# RFM69Pi_V3_1.net
KiCad netlist of a schematic drawn in EAGLE
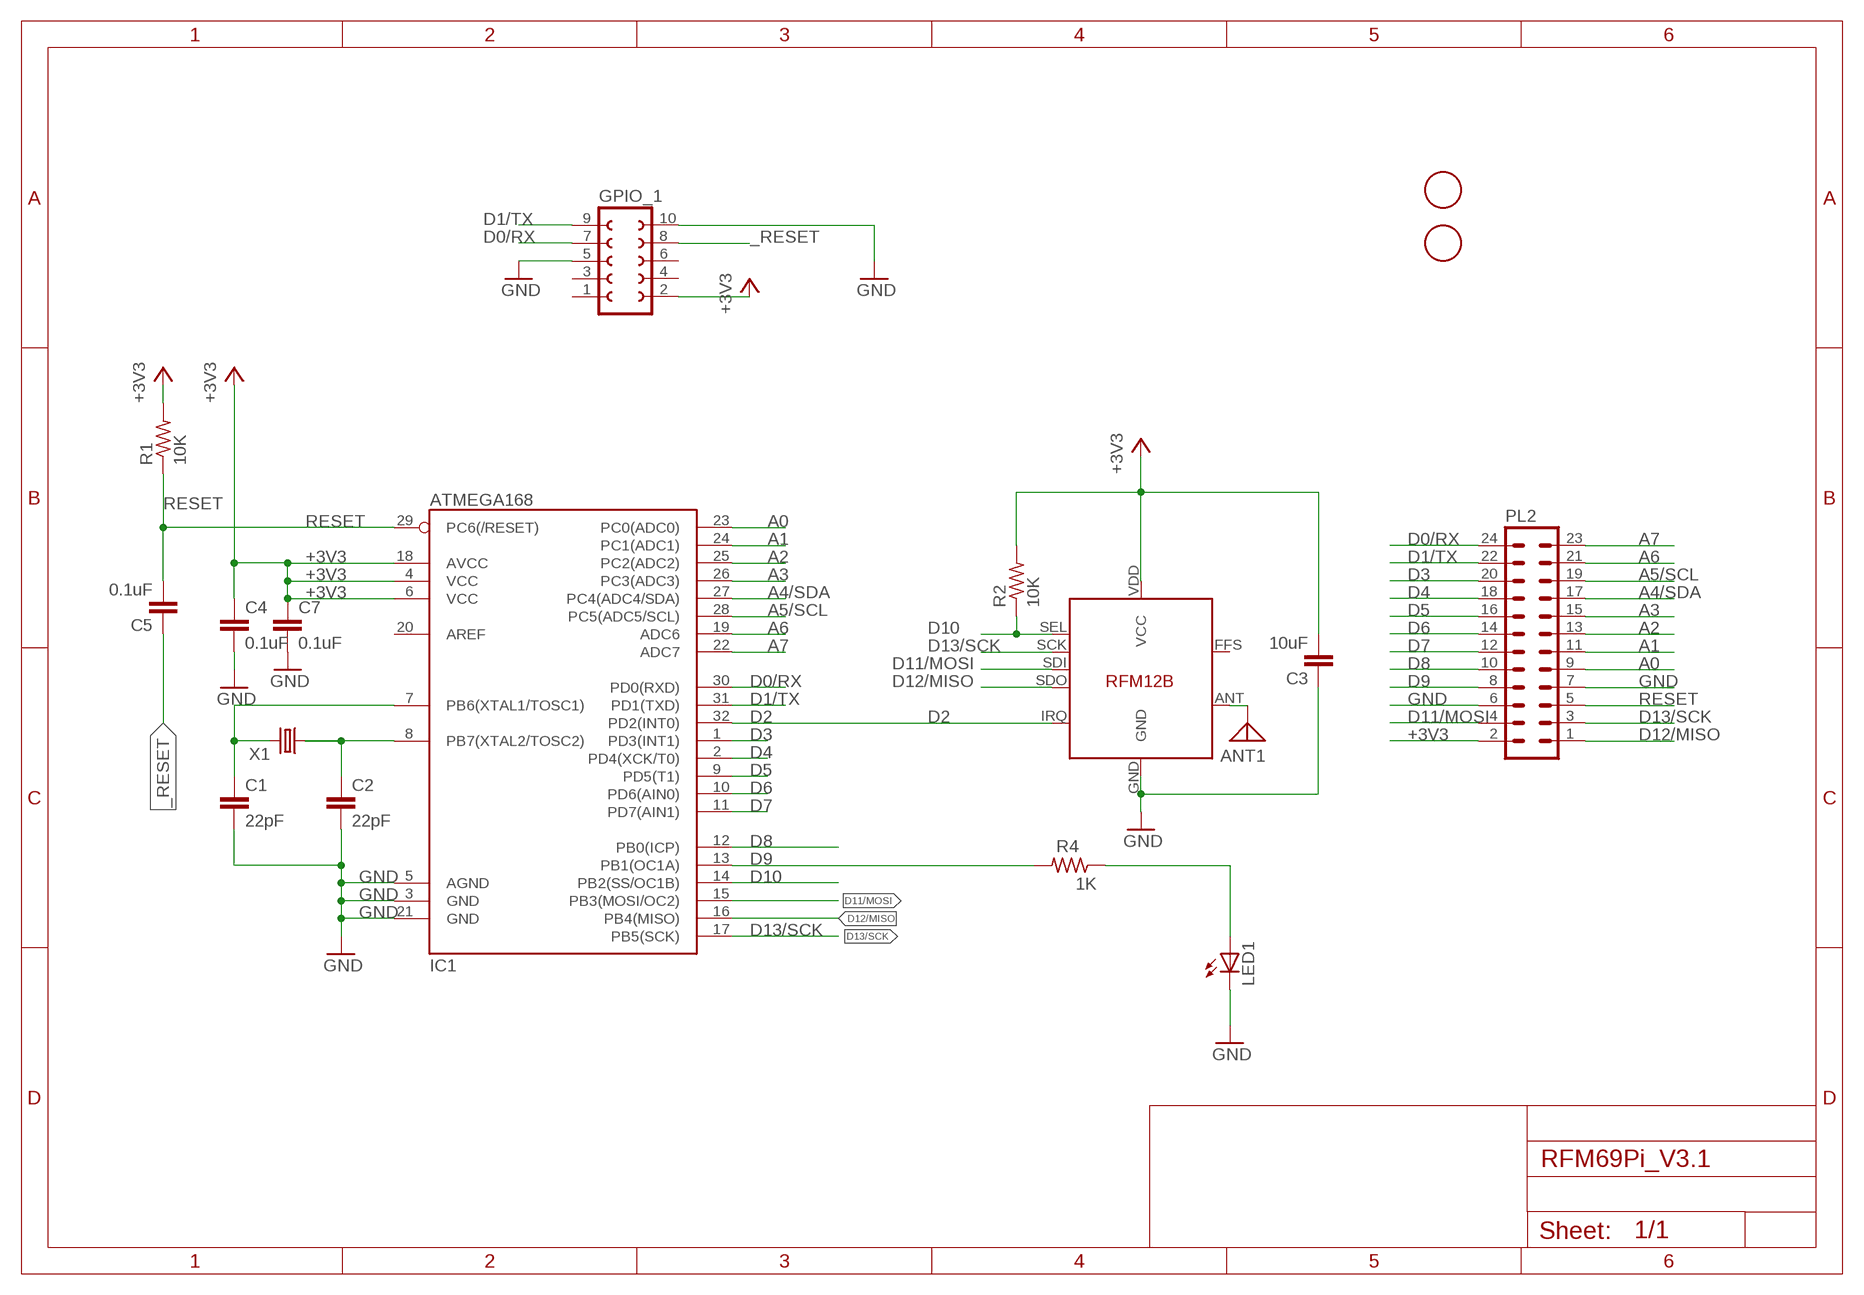
[diagram p0: schematic, sheet 1]

(export (version "E")
  (design (tool "Eeschema 10.0.6"))
  (components
    (comp (ref "ANT1")
      (value "ANTENNA")
      (footprint "eagle-import:PAD-01")
      (libsource (lib "eagle-import") (part "ANTENNA"))
    )
    (comp (ref "C1")
      (value "22pF")
      (footprint "eagle-import:C0603")
      (libsource (lib "eagle-import") (part "C-EUC0603"))
    )
    (comp (ref "C2")
      (value "22pF")
      (footprint "eagle-import:C0603")
      (libsource (lib "eagle-import") (part "C-EUC0603"))
    )
    (comp (ref "C3")
      (value "10uF")
      (footprint "eagle-import:C0603")
      (libsource (lib "eagle-import") (part "C-EUC0603"))
    )
    (comp (ref "C4")
      (value "0.1uF")
      (footprint "eagle-import:C0603")
      (libsource (lib "eagle-import") (part "C-EUC0603"))
    )
    (comp (ref "C5")
      (value "0.1uF")
      (footprint "eagle-import:C0603")
      (libsource (lib "eagle-import") (part "C-EUC0603"))
    )
    (comp (ref "C7")
      (value "0.1uF")
      (footprint "eagle-import:C0603")
      (libsource (lib "eagle-import") (part "resistor_C-EUC0603"))
    )
    (comp (ref "GPIO_1")
      (value "FE05-2")
      (footprint "eagle-import:FE05-2")
      (libsource (lib "eagle-import") (part "FE05-2"))
    )
    (comp (ref "IC1")
      (value "ATMEGA168")
      (footprint "eagle-import:TQFP32-08")
      (libsource (lib "eagle-import") (part "ATMEGA168"))
    )
    (comp (ref "LED1")
      (value "LEDSML0603")
      (footprint "eagle-import:SML0603")
      (libsource (lib "eagle-import") (part "LEDSML0603"))
    )
    (comp (ref "PL2")
      (value "MA12-2")
      (footprint "eagle-import:MA12-2")
      (libsource (lib "eagle-import") (part "MA12-2"))
    )
    (comp (ref "R1")
      (value "10K")
      (footprint "eagle-import:R0603")
      (libsource (lib "eagle-import") (part "R-US_R0603"))
    )
    (comp (ref "R2")
      (value "10K")
      (footprint "eagle-import:R0603")
      (libsource (lib "eagle-import") (part "R-US_R0603"))
    )
    (comp (ref "R4")
      (value "1K")
      (footprint "eagle-import:R0603")
      (libsource (lib "eagle-import") (part "R-US_R0603"))
    )
    (comp (ref "RFM12B-RFM69CW")
      (value "RFM12B")
      (footprint "eagle-import:RFM12B")
      (libsource (lib "eagle-import") (part "RFM12B"))
    )
    (comp (ref "U$1")
      (value "FIDUCIAL")
      (footprint "eagle-import:FIDUCIAL_1MM")
      (libsource (lib "eagle-import") (part "FIDUCIAL"))
    )
    (comp (ref "U$2")
      (value "FIDUCIAL")
      (footprint "eagle-import:FIDUCIAL_1MM")
      (libsource (lib "eagle-import") (part "FIDUCIAL"))
    )
    (comp (ref "X1")
      (value "CRYSTALHC49US")
      (footprint "eagle-import:HC49US")
      (libsource (lib "eagle-import") (part "CRYSTALHC49US"))
    )
  )
  (nets
    (net (code "1") (name "+3V3") (class "Default")
      (node (ref "C3") (pin "2") (pinfunction "2_2") (pintype "passive"))
      (node (ref "C4") (pin "1") (pinfunction "1_1") (pintype "passive"))
      (node (ref "C7") (pin "1") (pinfunction "1_1") (pintype "passive"))
      (node (ref "GPIO_1") (pin "2") (pinfunction "2_2") (pintype "passive"))
      (node (ref "IC1") (pin "18") (pinfunction "AVCC_18") (pintype "bidirectional"))
      (node (ref "IC1") (pin "4") (pinfunction "VCC_4") (pintype "bidirectional"))
      (node (ref "IC1") (pin "6") (pinfunction "VCC_6") (pintype "bidirectional"))
      (node (ref "PL2") (pin "2") (pinfunction "2_2") (pintype "passive"))
      (node (ref "R1") (pin "2") (pinfunction "2_2") (pintype "passive"))
      (node (ref "R2") (pin "2") (pinfunction "2_2") (pintype "passive"))
      (node (ref "RFM12B-RFM69CW") (pin "VDD") (pinfunction "VCC_VDD") (pintype "power_in"))
    )
    (net (code "2") (name "/A0") (class "Default")
      (node (ref "IC1") (pin "23") (pinfunction "PC0(ADC0)_23") (pintype "bidirectional"))
      (node (ref "PL2") (pin "9") (pinfunction "9_9") (pintype "passive"))
    )
    (net (code "3") (name "/A1") (class "Default")
      (node (ref "IC1") (pin "24") (pinfunction "PC1(ADC1)_24") (pintype "bidirectional"))
      (node (ref "PL2") (pin "11") (pinfunction "11_11") (pintype "passive"))
    )
    (net (code "4") (name "/A2") (class "Default")
      (node (ref "IC1") (pin "25") (pinfunction "PC2(ADC2)_25") (pintype "bidirectional"))
      (node (ref "PL2") (pin "13") (pinfunction "13_13") (pintype "passive"))
    )
    (net (code "5") (name "/A3") (class "Default")
      (node (ref "IC1") (pin "26") (pinfunction "PC3(ADC3)_26") (pintype "bidirectional"))
      (node (ref "PL2") (pin "15") (pinfunction "15_15") (pintype "passive"))
    )
    (net (code "6") (name "/A4{slash}SDA") (class "Default")
      (node (ref "IC1") (pin "27") (pinfunction "PC4(ADC4/SDA)_27") (pintype "bidirectional"))
      (node (ref "PL2") (pin "17") (pinfunction "17_17") (pintype "passive"))
    )
    (net (code "7") (name "/A5{slash}SCL") (class "Default")
      (node (ref "IC1") (pin "28") (pinfunction "PC5(ADC5/SCL)_28") (pintype "bidirectional"))
      (node (ref "PL2") (pin "19") (pinfunction "19_19") (pintype "passive"))
    )
    (net (code "8") (name "/A6") (class "Default")
      (node (ref "IC1") (pin "19") (pinfunction "ADC6_19") (pintype "bidirectional"))
      (node (ref "PL2") (pin "21") (pinfunction "21_21") (pintype "passive"))
    )
    (net (code "9") (name "/A7") (class "Default")
      (node (ref "IC1") (pin "22") (pinfunction "ADC7_22") (pintype "bidirectional"))
      (node (ref "PL2") (pin "23") (pinfunction "23_23") (pintype "passive"))
    )
    (net (code "10") (name "/D0{slash}RX") (class "Default")
      (node (ref "GPIO_1") (pin "7") (pinfunction "7_7") (pintype "passive"))
      (node (ref "IC1") (pin "30") (pinfunction "PD0(RXD)_30") (pintype "bidirectional"))
      (node (ref "PL2") (pin "24") (pinfunction "24_24") (pintype "passive"))
    )
    (net (code "11") (name "/D1{slash}TX") (class "Default")
      (node (ref "GPIO_1") (pin "9") (pinfunction "9_9") (pintype "passive"))
      (node (ref "IC1") (pin "31") (pinfunction "PD1(TXD)_31") (pintype "bidirectional"))
      (node (ref "PL2") (pin "22") (pinfunction "22_22") (pintype "passive"))
    )
    (net (code "12") (name "/D2") (class "Default")
      (node (ref "IC1") (pin "32") (pinfunction "PD2(INT0)_32") (pintype "bidirectional"))
      (node (ref "RFM12B-RFM69CW") (pin "IRQ") (pinfunction "IRQ_IRQ") (pintype "open_collector"))
    )
    (net (code "13") (name "/D3") (class "Default")
      (node (ref "IC1") (pin "1") (pinfunction "PD3(INT1)_1") (pintype "bidirectional"))
      (node (ref "PL2") (pin "20") (pinfunction "20_20") (pintype "passive"))
    )
    (net (code "14") (name "/D4") (class "Default")
      (node (ref "IC1") (pin "2") (pinfunction "PD4(XCK/T0)_2") (pintype "bidirectional"))
      (node (ref "PL2") (pin "18") (pinfunction "18_18") (pintype "passive"))
    )
    (net (code "15") (name "/D5") (class "Default")
      (node (ref "IC1") (pin "9") (pinfunction "PD5(T1)_9") (pintype "bidirectional"))
      (node (ref "PL2") (pin "16") (pinfunction "16_16") (pintype "passive"))
    )
    (net (code "16") (name "/D6") (class "Default")
      (node (ref "IC1") (pin "10") (pinfunction "PD6(AIN0)_10") (pintype "bidirectional"))
      (node (ref "PL2") (pin "14") (pinfunction "14_14") (pintype "passive"))
    )
    (net (code "17") (name "/D7") (class "Default")
      (node (ref "IC1") (pin "11") (pinfunction "PD7(AIN1)_11") (pintype "bidirectional"))
      (node (ref "PL2") (pin "12") (pinfunction "12_12") (pintype "passive"))
    )
    (net (code "18") (name "/D8") (class "Default")
      (node (ref "IC1") (pin "12") (pinfunction "PB0(ICP)_12") (pintype "bidirectional"))
      (node (ref "PL2") (pin "10") (pinfunction "10_10") (pintype "passive"))
    )
    (net (code "19") (name "/D9") (class "Default")
      (node (ref "IC1") (pin "13") (pinfunction "PB1(OC1A)_13") (pintype "bidirectional"))
      (node (ref "PL2") (pin "8") (pinfunction "8_8") (pintype "passive"))
      (node (ref "R4") (pin "2") (pinfunction "2_2") (pintype "passive"))
    )
    (net (code "20") (name "/D10") (class "Default")
      (node (ref "IC1") (pin "14") (pinfunction "PB2(SS/OC1B)_14") (pintype "bidirectional"))
      (node (ref "R2") (pin "1") (pinfunction "1_1") (pintype "passive"))
      (node (ref "RFM12B-RFM69CW") (pin "SEL") (pinfunction "SEL_SEL") (pintype "input"))
    )
    (net (code "21") (name "/RESET") (class "Default")
      (node (ref "C5") (pin "2") (pinfunction "2_2") (pintype "passive"))
      (node (ref "IC1") (pin "29") (pinfunction "PC6(/RESET)_29") (pintype "bidirectional"))
      (node (ref "PL2") (pin "5") (pinfunction "5_5") (pintype "passive"))
      (node (ref "R1") (pin "1") (pinfunction "1_1") (pintype "passive"))
    )
    (net (code "22") (name "D11{slash}MOSI") (class "Default")
      (node (ref "IC1") (pin "15") (pinfunction "PB3(MOSI/OC2)_15") (pintype "bidirectional"))
      (node (ref "PL2") (pin "4") (pinfunction "4_4") (pintype "passive"))
      (node (ref "RFM12B-RFM69CW") (pin "SDI") (pinfunction "SDI_SDI") (pintype "input"))
    )
    (net (code "23") (name "D12{slash}MISO") (class "Default")
      (node (ref "IC1") (pin "16") (pinfunction "PB4(MISO)_16") (pintype "bidirectional"))
      (node (ref "PL2") (pin "1") (pinfunction "1_1") (pintype "passive"))
      (node (ref "RFM12B-RFM69CW") (pin "SDO") (pinfunction "SDO_SDO") (pintype "output"))
    )
    (net (code "24") (name "D13{slash}SCK") (class "Default")
      (node (ref "IC1") (pin "17") (pinfunction "PB5(SCK)_17") (pintype "bidirectional"))
      (node (ref "PL2") (pin "3") (pinfunction "3_3") (pintype "passive"))
      (node (ref "RFM12B-RFM69CW") (pin "SCK") (pinfunction "SCK_SCK") (pintype "input"))
    )
    (net (code "25") (name "GND") (class "Default")
      (node (ref "C1") (pin "2") (pinfunction "2_2") (pintype "passive"))
      (node (ref "C2") (pin "2") (pinfunction "2_2") (pintype "passive"))
      (node (ref "C3") (pin "1") (pinfunction "1_1") (pintype "passive"))
      (node (ref "C4") (pin "2") (pinfunction "2_2") (pintype "passive"))
      (node (ref "C7") (pin "2") (pinfunction "2_2") (pintype "passive"))
      (node (ref "GPIO_1") (pin "10") (pinfunction "10_10") (pintype "passive"))
      (node (ref "GPIO_1") (pin "5") (pinfunction "5_5") (pintype "passive"))
      (node (ref "IC1") (pin "21") (pinfunction "GND_21") (pintype "bidirectional"))
      (node (ref "IC1") (pin "3") (pinfunction "GND_3") (pintype "bidirectional"))
      (node (ref "IC1") (pin "5") (pinfunction "AGND_5") (pintype "bidirectional"))
      (node (ref "LED1") (pin "C") (pinfunction "C_C") (pintype "passive"))
      (node (ref "PL2") (pin "6") (pinfunction "6_6") (pintype "passive"))
      (node (ref "PL2") (pin "7") (pinfunction "7_7") (pintype "passive"))
      (node (ref "RFM12B-RFM69CW") (pin "GND") (pinfunction "GND_GND") (pintype "power_in"))
    )
    (net (code "26") (name "Net-(ANT1-Pad1)") (class "Default")
      (node (ref "ANT1") (pin "1") (pinfunction "1_1") (pintype "output"))
      (node (ref "RFM12B-RFM69CW") (pin "ANT") (pinfunction "ANT_ANT") (pintype "passive"))
    )
    (net (code "27") (name "Net-(IC1-PB6(XTAL1{slash}TOSC1))") (class "Default")
      (node (ref "C1") (pin "1") (pinfunction "1_1") (pintype "passive"))
      (node (ref "IC1") (pin "7") (pinfunction "PB6(XTAL1/TOSC1)_7") (pintype "bidirectional"))
      (node (ref "X1") (pin "2") (pinfunction "2_2") (pintype "passive"))
    )
    (net (code "28") (name "Net-(IC1-PB7(XTAL2{slash}TOSC2))") (class "Default")
      (node (ref "C2") (pin "1") (pinfunction "1_1") (pintype "passive"))
      (node (ref "IC1") (pin "8") (pinfunction "PB7(XTAL2/TOSC2)_8") (pintype "bidirectional"))
      (node (ref "X1") (pin "1") (pinfunction "1_1") (pintype "passive"))
    )
    (net (code "29") (name "Net-(LED1-PadA)") (class "Default")
      (node (ref "LED1") (pin "A") (pinfunction "A_A") (pintype "passive"))
      (node (ref "R4") (pin "1") (pinfunction "1_1") (pintype "passive"))
    )
    (net (code "30") (name "_RESET") (class "Default")
      (node (ref "C5") (pin "1") (pinfunction "1_1") (pintype "passive"))
      (node (ref "GPIO_1") (pin "8") (pinfunction "8_8") (pintype "passive"))
    )
    (net (code "31") (name "unconnected-(GPIO_1-Pad1)") (class "Default")
      (node (ref "GPIO_1") (pin "1") (pinfunction "1_1") (pintype "passive"))
    )
    (net (code "32") (name "unconnected-(GPIO_1-Pad3)") (class "Default")
      (node (ref "GPIO_1") (pin "3") (pinfunction "3_3") (pintype "passive"))
    )
    (net (code "33") (name "unconnected-(GPIO_1-Pad4)") (class "Default")
      (node (ref "GPIO_1") (pin "4") (pinfunction "4_4") (pintype "passive"))
    )
    (net (code "34") (name "unconnected-(GPIO_1-Pad6)") (class "Default")
      (node (ref "GPIO_1") (pin "6") (pinfunction "6_6") (pintype "passive"))
    )
    (net (code "35") (name "unconnected-(IC1-AREF-Pad20)") (class "Default")
      (node (ref "IC1") (pin "20") (pinfunction "AREF_20") (pintype "bidirectional"))
    )
    (net (code "36") (name "unconnected-(RFM12B-RFM69CW-PadFFS)") (class "Default")
      (node (ref "RFM12B-RFM69CW") (pin "FFS") (pinfunction "FFS_FFS") (pintype "bidirectional"))
    )
  )
)
